# mach_master.net
KiCad netlist of a schematic drawn in Altium Designer
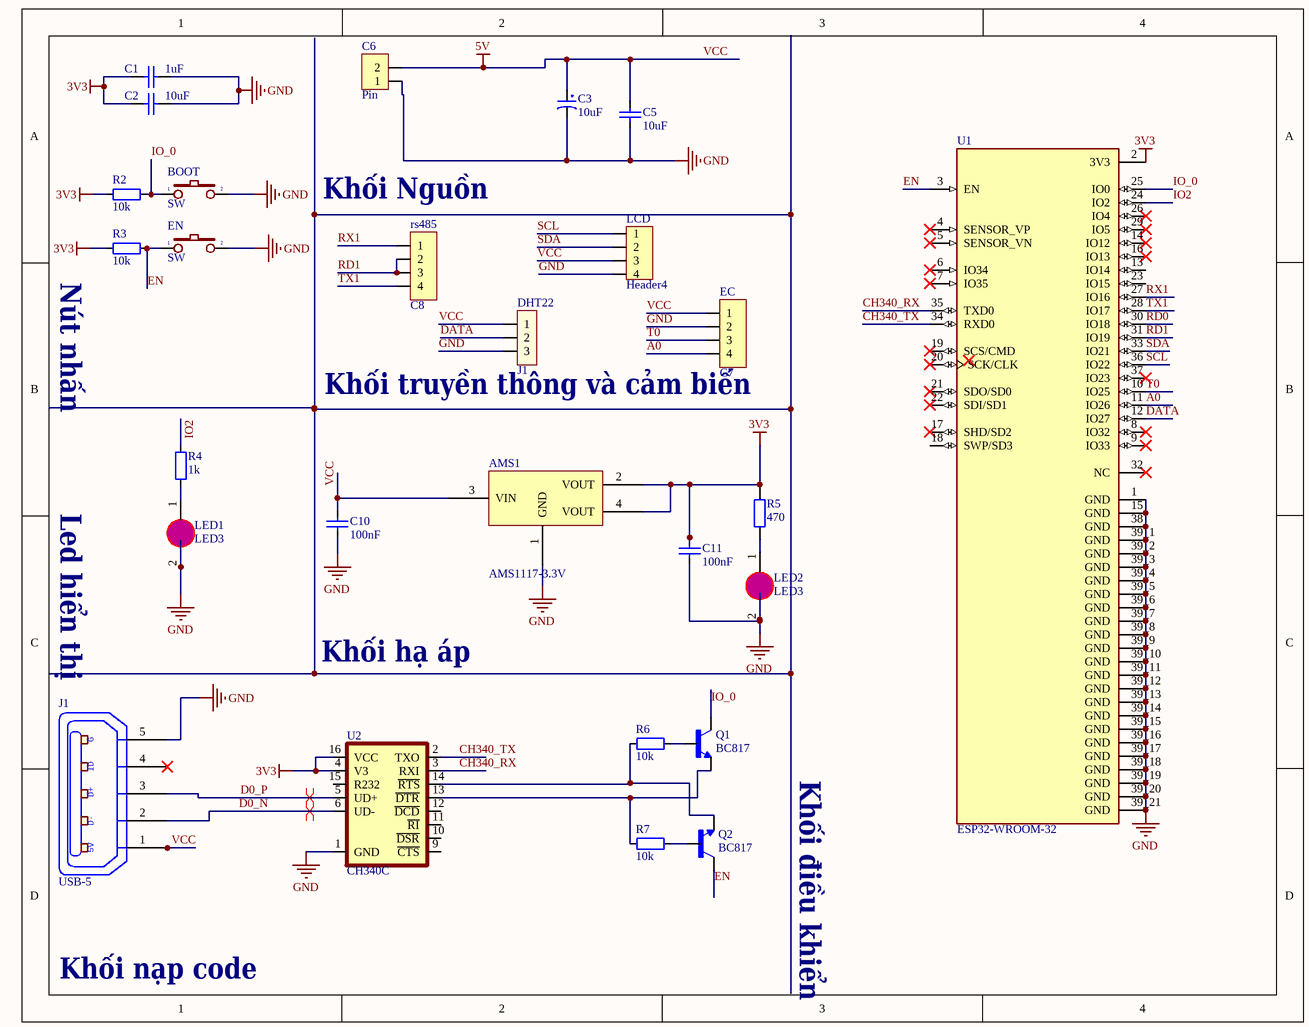
[diagram p0: mach master.SchDoc]

(export (version "E")
  (design (tool "Eeschema 10.0.6"))
  (components
    (comp (ref "AMS1")
      (value "AMS1117-3.3V")
      (footprint "SOT223")
      (description "Dán")
      (libsource (lib "IC") (part "AMS1117 SMD"))
    )
    (comp (ref "BOOT")
      (value "SW")
      (footprint "SW-SMD")
      (description "Switch button 2 pin")
      (libsource (lib "My Library") (part "SW2"))
    )
    (comp (ref "C1")
      (value "1uF")
      (footprint "CAP_0805")
      (description "Capacitor")
      (fields (field (name "PUBLISHER") "Altium Limited"))
      (libsource (lib "") (part "CapSMD_1"))
    )
    (comp (ref "C2")
      (value "10uF")
      (footprint "CAP_0805")
      (description "Capacitor")
      (fields (field (name "PUBLISHER") "Altium Limited"))
      (libsource (lib "") (part "CapSMD_1"))
    )
    (comp (ref "C3")
      (value "10uF")
      (footprint "tu tantalum smd3216")
      (description "Dán")
      (libsource (lib "Tu dien") (part "Tu tantalum 10uF 16V SMD3216"))
    )
    (comp (ref "C5")
      (value "10uF")
      (footprint "CAP_0805")
      (description "Capacitor")
      (fields (field (name "PUBLISHER") "Altium Limited"))
      (libsource (lib "My Library") (part "CapSMD"))
    )
    (comp (ref "C6")
      (value "Pin")
      (footprint "KF2-5.08")
      (description "Header IDC, 2 x 1 Pin Vertical 2.54mm Pitch (Non-Boxed, Male)")
      (fields
        (field (name "MANUFACTURER") "Würth Elektronik eiSos GmbH")
        (field (name "PARTNO") "613002143121")
        (field (name "CREATED BY") "Karrer Zheng")
      )
      (libsource (lib "My Library") (part "Header2"))
    )
    (comp (ref "C10")
      (value "100nF")
      (footprint "CAP_0805")
      (description "Capacitor")
      (fields (field (name "PUBLISHER") "Altium Limited"))
      (libsource (lib "My Library") (part "CapSMD"))
    )
    (comp (ref "C11")
      (value "100nF")
      (footprint "CAP_0805")
      (description "Capacitor")
      (fields (field (name "PUBLISHER") "Altium Limited"))
      (libsource (lib "My Library") (part "CapSMD"))
    )
    (comp (ref "DHT22")
      (value "J1")
      (footprint "Header3")
      (description "Jumper 3")
      (libsource (lib "My Library") (part "JP3"))
    )
    (comp (ref "EC")
      (value "C7")
      (footprint "Header4")
      (description "WR-PHD 2.54 mm Angled Socket Header")
      (fields
        (field (name "MANUFACTURER") "Würth Elektronik eiSos GmbH")
        (field (name "PARTNO") "613004143121")
        (field (name "CREATED BY") "Karrer Zheng")
      )
      (libsource (lib "My Library") (part "JP4"))
    )
    (comp (ref "EN")
      (value "SW")
      (footprint "SW-SMD")
      (description "Switch button 2 pin")
      (libsource (lib "My Library") (part "SW2"))
    )
    (comp (ref "J1")
      (value "USB-5")
      (footprint "USB-M1")
      (fields
        (field (name "MANUFACTURER") "FCI")
        (field (name "MANUFACTURER PART NUMBER") "10118193-0001LF")
        (field (name ".CREATOR") "MM")
        (field (name ".CHECKED PCB") "RF")
        (field (name ".CHECKED SCH") "MM")
      )
      (libsource (lib "My Library 2") (part "USB-5"))
    )
    (comp (ref "LCD")
      (value "Header4")
      (footprint "Header4")
      (description "Header IDC, 4 x 1 Pin Vertical 2.54mm Pitch (Non-Boxed, Male)")
      (fields
        (field (name "MANUFACTURER") "Würth Elektronik eiSos GmbH")
        (field (name "PARTNO") "613002143121")
        (field (name "CREATED BY") "Karrer Zheng")
      )
      (libsource (lib "My Library") (part "Header4"))
    )
    (comp (ref "LED1")
      (value "LED3")
      (footprint "LED0805")
      (description "LED SMD 0805")
      (libsource (lib "My Library 2") (part "LED0805"))
    )
    (comp (ref "LED2")
      (value "LED3")
      (footprint "LED0805")
      (description "LED SMD 0805")
      (libsource (lib "My Library 2") (part "LED0805"))
    )
    (comp (ref "Q1")
      (value "BC817")
      (footprint "SOT95P240X97-3N")
      (description "Bipolar (BJT) Transistor NPN 45V 500mA 100MHz 250mW Surface Mount TO-236AB")
      (fields (field (name "MF") "Rectron"))
      (libsource (lib "BC817") (part "BC817"))
    )
    (comp (ref "Q2")
      (value "BC817")
      (footprint "SOT95P240X97-3N")
      (description "Bipolar (BJT) Transistor NPN 45V 500mA 100MHz 250mW Surface Mount TO-236AB")
      (fields (field (name "MF") "Rectron"))
      (libsource (lib "") (part "BC817_1"))
    )
    (comp (ref "R2")
      (value "10k")
      (footprint "RES-SMD-0805")
      (description "Resistor")
      (fields
        (field (name "MANUFACTURER") "Generic Components")
        (field (name "PUBLISHER") "Altium Hobart Technology Centre")
      )
      (libsource (lib "My Library") (part "Resistor - SMD"))
    )
    (comp (ref "R3")
      (value "10k")
      (footprint "RES-SMD-0805")
      (description "Resistor")
      (fields
        (field (name "MANUFACTURER") "Generic Components")
        (field (name "PUBLISHER") "Altium Hobart Technology Centre")
      )
      (libsource (lib "My Library") (part "Resistor - SMD"))
    )
    (comp (ref "R4")
      (value "1k")
      (footprint "RES-SMD-0805")
      (description "Resistor")
      (fields
        (field (name "MANUFACTURER") "Generic Components")
        (field (name "PUBLISHER") "Altium Hobart Technology Centre")
      )
      (libsource (lib "My Library") (part "Resistor - SMD"))
    )
    (comp (ref "R5")
      (value "470")
      (footprint "RES-SMD-0805")
      (description "22")
      (fields
        (field (name "MANUFACTURER") "Generic Components")
        (field (name "PUBLISHER") "Altium Hobart Technology Centre")
      )
      (libsource (lib "") (part "Resistor - SMD_1"))
    )
    (comp (ref "R6")
      (value "10k")
      (footprint "RES-SMD-0805")
      (description "Resistor")
      (fields
        (field (name "MANUFACTURER") "Generic Components")
        (field (name "PUBLISHER") "Altium Hobart Technology Centre")
      )
      (libsource (lib "My Library") (part "Resistor - SMD"))
    )
    (comp (ref "R7")
      (value "10k")
      (footprint "RES-SMD-0805")
      (description "Resistor")
      (fields
        (field (name "MANUFACTURER") "Generic Components")
        (field (name "PUBLISHER") "Altium Hobart Technology Centre")
      )
      (libsource (lib "My Library") (part "Resistor - SMD"))
    )
    (comp (ref "rs485")
      (value "C8")
      (footprint "Header4")
      (description "WR-PHD 2.54 mm Angled Socket Header")
      (fields
        (field (name "MANUFACTURER") "Würth Elektronik eiSos GmbH")
        (field (name "PARTNO") "613004143121")
        (field (name "CREATED BY") "Karrer Zheng")
      )
      (libsource (lib "My Library") (part "JP4"))
    )
    (comp (ref "U1")
      (value "ESP32-WROOM-32")
      (footprint "MODULE_ESP32-WROOM-32")
      (fields (field (name "MF") "Espressif Systems"))
      (libsource (lib "ESP32-WROOM-32") (part "ESP32-WROOM-32"))
    )
    (comp (ref "U2")
      (value "CH340C")
      (footprint "SOP-16")
      (description "USB to serial chip CH340")
      (fields (field (name "MF") "WCH"))
      (libsource (lib "My Library") (part "CH340C"))
    )
  )
  (nets
    (net (code "1") (name "/A0") (class "Default")
      (node (ref "EC") (pin "4") (pinfunction "4_4") (pintype "passive"))
      (node (ref "U1") (pin "11") (pinfunction "IO26_11") (pintype "bidirectional"))
    )
    (net (code "2") (name "/CH340_RX") (class "Default")
      (node (ref "U1") (pin "35") (pinfunction "TXD0_35") (pintype "bidirectional"))
      (node (ref "U2") (pin "3") (pinfunction "RXI_3") (pintype "bidirectional"))
    )
    (net (code "3") (name "/CH340_TX") (class "Default")
      (node (ref "U1") (pin "34") (pinfunction "RXD0_34") (pintype "bidirectional"))
      (node (ref "U2") (pin "2") (pinfunction "TXO_2") (pintype "bidirectional"))
    )
    (net (code "4") (name "/D0_N") (class "Default")
      (node (ref "J1") (pin "2") (pinfunction "P2_2") (pintype "passive"))
      (node (ref "U2") (pin "6") (pinfunction "UD-_6") (pintype "bidirectional"))
    )
    (net (code "5") (name "/D0_P") (class "Default")
      (node (ref "J1") (pin "3") (pinfunction "P3_3") (pintype "passive"))
      (node (ref "U2") (pin "5") (pinfunction "UD+_5") (pintype "bidirectional"))
    )
    (net (code "6") (name "/DATA") (class "Default")
      (node (ref "DHT22") (pin "2") (pinfunction "2_2") (pintype "passive"))
      (node (ref "U1") (pin "12") (pinfunction "IO27_12") (pintype "bidirectional"))
    )
    (net (code "7") (name "/EN") (class "Default")
      (node (ref "EN") (pin "1") (pinfunction "1_1") (pintype "passive"))
      (node (ref "Q2") (pin "3") (pinfunction "C_3") (pintype "passive"))
      (node (ref "R3") (pin "1") (pinfunction "1_1") (pintype "passive"))
      (node (ref "U1") (pin "3") (pinfunction "EN_3") (pintype "input"))
    )
    (net (code "8") (name "/IO2") (class "Default")
      (node (ref "R4") (pin "2") (pinfunction "2_2") (pintype "passive"))
      (node (ref "U1") (pin "24") (pinfunction "IO2_24") (pintype "bidirectional"))
    )
    (net (code "9") (name "/IO_0") (class "Default")
      (node (ref "BOOT") (pin "1") (pinfunction "1_1") (pintype "passive"))
      (node (ref "Q1") (pin "3") (pinfunction "C_3") (pintype "passive"))
      (node (ref "R2") (pin "1") (pinfunction "1_1") (pintype "passive"))
      (node (ref "U1") (pin "25") (pinfunction "IO0_25") (pintype "bidirectional"))
    )
    (net (code "10") (name "/RD0") (class "Default")
      (node (ref "U1") (pin "30") (pinfunction "IO18_30") (pintype "bidirectional"))
    )
    (net (code "11") (name "/RD1") (class "Default")
      (node (ref "U1") (pin "31") (pinfunction "IO19_31") (pintype "bidirectional"))
      (node (ref "rs485") (pin "2") (pinfunction "2_2") (pintype "passive"))
      (node (ref "rs485") (pin "3") (pinfunction "3_3") (pintype "passive"))
    )
    (net (code "12") (name "/RX1") (class "Default")
      (node (ref "U1") (pin "27") (pinfunction "IO16_27") (pintype "bidirectional"))
      (node (ref "rs485") (pin "1") (pinfunction "1_1") (pintype "passive"))
    )
    (net (code "13") (name "/SCL") (class "Default")
      (node (ref "LCD") (pin "1") (pinfunction "1_1") (pintype "passive"))
      (node (ref "U1") (pin "36") (pinfunction "IO22_36") (pintype "bidirectional"))
    )
    (net (code "14") (name "/SDA") (class "Default")
      (node (ref "LCD") (pin "2") (pinfunction "2_2") (pintype "passive"))
      (node (ref "U1") (pin "33") (pinfunction "IO21_33") (pintype "bidirectional"))
    )
    (net (code "15") (name "/T0") (class "Default")
      (node (ref "EC") (pin "3") (pinfunction "3_3") (pintype "passive"))
      (node (ref "U1") (pin "10") (pinfunction "IO25_10") (pintype "bidirectional"))
    )
    (net (code "16") (name "/TX1") (class "Default")
      (node (ref "U1") (pin "28") (pinfunction "IO17_28") (pintype "bidirectional"))
      (node (ref "rs485") (pin "4") (pinfunction "4_4") (pintype "passive"))
    )
    (net (code "17") (name "3V3") (class "Default")
      (node (ref "AMS1") (pin "2") (pinfunction "VOUT_2") (pintype "passive"))
      (node (ref "AMS1") (pin "4") (pinfunction "VOUT_4") (pintype "passive"))
      (node (ref "C1") (pin "1") (pinfunction "1_1") (pintype "passive"))
      (node (ref "C11") (pin "2") (pinfunction "2_2") (pintype "passive"))
      (node (ref "C2") (pin "1") (pinfunction "1_1") (pintype "passive"))
      (node (ref "R2") (pin "2") (pinfunction "2_2") (pintype "passive"))
      (node (ref "R3") (pin "2") (pinfunction "2_2") (pintype "passive"))
      (node (ref "R5") (pin "1") (pinfunction "1_1") (pintype "passive"))
      (node (ref "U1") (pin "2") (pinfunction "3V3_2") (pintype "power_in"))
      (node (ref "U2") (pin "16") (pinfunction "VCC_16") (pintype "bidirectional"))
      (node (ref "U2") (pin "4") (pinfunction "V3_4") (pintype "bidirectional"))
    )
    (net (code "18") (name "5V") (class "Default")
      (node (ref "AMS1") (pin "3") (pinfunction "VIN_3") (pintype "passive"))
      (node (ref "C10") (pin "2") (pinfunction "2_2") (pintype "passive"))
      (node (ref "C3") (pin "1") (pinfunction "1_1") (pintype "passive"))
      (node (ref "C5") (pin "2") (pinfunction "2_2") (pintype "passive"))
      (node (ref "C6") (pin "2") (pinfunction "2_2") (pintype "passive"))
      (node (ref "DHT22") (pin "1") (pinfunction "1_1") (pintype "passive"))
      (node (ref "EC") (pin "1") (pinfunction "1_1") (pintype "passive"))
      (node (ref "J1") (pin "1") (pinfunction "P1_1") (pintype "passive"))
      (node (ref "LCD") (pin "3") (pinfunction "3_3") (pintype "passive"))
    )
    (net (code "19") (name "GND") (class "Default")
      (node (ref "AMS1") (pin "1") (pinfunction "GND_1") (pintype "passive"))
      (node (ref "BOOT") (pin "2") (pinfunction "2_2") (pintype "passive"))
      (node (ref "C1") (pin "2") (pinfunction "2_2") (pintype "passive"))
      (node (ref "C10") (pin "1") (pinfunction "1_1") (pintype "passive"))
      (node (ref "C11") (pin "1") (pinfunction "1_1") (pintype "passive"))
      (node (ref "C2") (pin "2") (pinfunction "2_2") (pintype "passive"))
      (node (ref "C3") (pin "2") (pinfunction "2_2") (pintype "passive"))
      (node (ref "C5") (pin "1") (pinfunction "1_1") (pintype "passive"))
      (node (ref "C6") (pin "1") (pinfunction "1_1") (pintype "passive"))
      (node (ref "DHT22") (pin "3") (pinfunction "3_3") (pintype "passive"))
      (node (ref "EC") (pin "2") (pinfunction "2_2") (pintype "passive"))
      (node (ref "EN") (pin "2") (pinfunction "2_2") (pintype "passive"))
      (node (ref "J1") (pin "5") (pinfunction "P5_5") (pintype "passive"))
      (node (ref "LCD") (pin "4") (pinfunction "4_4") (pintype "passive"))
      (node (ref "LED1") (pin "2") (pinfunction "K_2") (pintype "passive"))
      (node (ref "LED2") (pin "2") (pinfunction "K_2") (pintype "passive"))
      (node (ref "U1") (pin "1") (pinfunction "GND_1") (pintype "power_in"))
      (node (ref "U1") (pin "15") (pinfunction "GND_15") (pintype "power_in"))
      (node (ref "U1") (pin "38") (pinfunction "GND_38") (pintype "power_in"))
      (node (ref "U1") (pin "39_1") (pinfunction "GND_39_1") (pintype "power_in"))
      (node (ref "U1") (pin "39_10") (pinfunction "GND_39_10") (pintype "power_in"))
      (node (ref "U1") (pin "39_11") (pinfunction "GND_39_11") (pintype "power_in"))
      (node (ref "U1") (pin "39_12") (pinfunction "GND_39_12") (pintype "power_in"))
      (node (ref "U1") (pin "39_13") (pinfunction "GND_39_13") (pintype "power_in"))
      (node (ref "U1") (pin "39_14") (pinfunction "GND_39_14") (pintype "power_in"))
      (node (ref "U1") (pin "39_15") (pinfunction "GND_39_15") (pintype "power_in"))
      (node (ref "U1") (pin "39_16") (pinfunction "GND_39_16") (pintype "power_in"))
      (node (ref "U1") (pin "39_17") (pinfunction "GND_39_17") (pintype "power_in"))
      (node (ref "U1") (pin "39_18") (pinfunction "GND_39_18") (pintype "power_in"))
      (node (ref "U1") (pin "39_19") (pinfunction "GND_39_19") (pintype "power_in"))
      (node (ref "U1") (pin "39_2") (pinfunction "GND_39_2") (pintype "power_in"))
      (node (ref "U1") (pin "39_20") (pinfunction "GND_39_20") (pintype "power_in"))
      (node (ref "U1") (pin "39_21") (pinfunction "GND_39_21") (pintype "power_in"))
      (node (ref "U1") (pin "39_3") (pinfunction "GND_39_3") (pintype "power_in"))
      (node (ref "U1") (pin "39_4") (pinfunction "GND_39_4") (pintype "power_in"))
      (node (ref "U1") (pin "39_5") (pinfunction "GND_39_5") (pintype "power_in"))
      (node (ref "U1") (pin "39_6") (pinfunction "GND_39_6") (pintype "power_in"))
      (node (ref "U1") (pin "39_7") (pinfunction "GND_39_7") (pintype "power_in"))
      (node (ref "U1") (pin "39_8") (pinfunction "GND_39_8") (pintype "power_in"))
      (node (ref "U1") (pin "39_9") (pinfunction "GND_39_9") (pintype "power_in"))
      (node (ref "U2") (pin "1") (pinfunction "GND_1") (pintype "bidirectional"))
    )
    (net (code "20") (name "Net-(LED1-A)") (class "Default")
      (node (ref "LED1") (pin "1") (pinfunction "A_1") (pintype "passive"))
      (node (ref "R4") (pin "1") (pinfunction "1_1") (pintype "passive"))
    )
    (net (code "21") (name "Net-(LED2-A)") (class "Default")
      (node (ref "LED2") (pin "1") (pinfunction "A_1") (pintype "passive"))
      (node (ref "R5") (pin "2") (pinfunction "2_2") (pintype "passive"))
    )
    (net (code "22") (name "Net-(Q1-B)") (class "Default")
      (node (ref "Q1") (pin "1") (pinfunction "B_1") (pintype "passive"))
      (node (ref "R6") (pin "1") (pinfunction "1_1") (pintype "passive"))
    )
    (net (code "23") (name "Net-(Q1-E)") (class "Default")
      (node (ref "Q1") (pin "2") (pinfunction "E_2") (pintype "passive"))
      (node (ref "R7") (pin "2") (pinfunction "2_2") (pintype "passive"))
      (node (ref "U2") (pin "13") (pinfunction "~{DTR}_13") (pintype "bidirectional"))
    )
    (net (code "24") (name "Net-(Q2-B)") (class "Default")
      (node (ref "Q2") (pin "1") (pinfunction "B_1") (pintype "passive"))
      (node (ref "R7") (pin "1") (pinfunction "1_1") (pintype "passive"))
    )
    (net (code "25") (name "Net-(Q2-E)") (class "Default")
      (node (ref "Q2") (pin "2") (pinfunction "E_2") (pintype "passive"))
      (node (ref "R6") (pin "2") (pinfunction "2_2") (pintype "passive"))
      (node (ref "U2") (pin "14") (pinfunction "~{RTS}_14") (pintype "bidirectional"))
    )
    (net (code "26") (name "unconnected-(J1-P4-Pad4)") (class "Default")
      (node (ref "J1") (pin "4") (pinfunction "P4_4") (pintype "passive+no_connect"))
    )
    (net (code "27") (name "unconnected-(U1-IO4-Pad26)") (class "Default")
      (node (ref "U1") (pin "26") (pinfunction "IO4_26") (pintype "bidirectional+no_connect"))
    )
    (net (code "28") (name "unconnected-(U1-IO5-Pad29)") (class "Default")
      (node (ref "U1") (pin "29") (pinfunction "IO5_29") (pintype "bidirectional+no_connect"))
    )
    (net (code "29") (name "unconnected-(U1-IO12-Pad14)") (class "Default")
      (node (ref "U1") (pin "14") (pinfunction "IO12_14") (pintype "bidirectional+no_connect"))
    )
    (net (code "30") (name "unconnected-(U1-IO13-Pad16)") (class "Default")
      (node (ref "U1") (pin "16") (pinfunction "IO13_16") (pintype "bidirectional+no_connect"))
    )
    (net (code "31") (name "unconnected-(U1-IO14-Pad13)") (class "Default")
      (node (ref "U1") (pin "13") (pinfunction "IO14_13") (pintype "bidirectional"))
    )
    (net (code "32") (name "unconnected-(U1-IO15-Pad23)") (class "Default")
      (node (ref "U1") (pin "23") (pinfunction "IO15_23") (pintype "bidirectional"))
    )
    (net (code "33") (name "unconnected-(U1-IO23-Pad37)") (class "Default")
      (node (ref "U1") (pin "37") (pinfunction "IO23_37") (pintype "bidirectional+no_connect"))
    )
    (net (code "34") (name "unconnected-(U1-IO32-Pad8)") (class "Default")
      (node (ref "U1") (pin "8") (pinfunction "IO32_8") (pintype "bidirectional+no_connect"))
    )
    (net (code "35") (name "unconnected-(U1-IO33-Pad9)") (class "Default")
      (node (ref "U1") (pin "9") (pinfunction "IO33_9") (pintype "bidirectional+no_connect"))
    )
    (net (code "36") (name "unconnected-(U1-IO34-Pad6)") (class "Default")
      (node (ref "U1") (pin "6") (pinfunction "IO34_6") (pintype "input+no_connect"))
    )
    (net (code "37") (name "unconnected-(U1-IO35-Pad7)") (class "Default")
      (node (ref "U1") (pin "7") (pinfunction "IO35_7") (pintype "input+no_connect"))
    )
    (net (code "38") (name "unconnected-(U1-NC-Pad32)") (class "Default")
      (node (ref "U1") (pin "32") (pinfunction "NC_32") (pintype "passive+no_connect"))
    )
    (net (code "39") (name "unconnected-(U1-SCK{slash}CLK-Pad20)") (class "Default")
      (node (ref "U1") (pin "20") (pinfunction "SCK/CLK_20") (pintype "bidirectional+no_connect"))
    )
    (net (code "40") (name "unconnected-(U1-SCS{slash}CMD-Pad19)") (class "Default")
      (node (ref "U1") (pin "19") (pinfunction "SCS/CMD_19") (pintype "bidirectional+no_connect"))
    )
    (net (code "41") (name "unconnected-(U1-SDI{slash}SD1-Pad22)") (class "Default")
      (node (ref "U1") (pin "22") (pinfunction "SDI/SD1_22") (pintype "bidirectional+no_connect"))
    )
    (net (code "42") (name "unconnected-(U1-SDO{slash}SD0-Pad21)") (class "Default")
      (node (ref "U1") (pin "21") (pinfunction "SDO/SD0_21") (pintype "bidirectional+no_connect"))
    )
    (net (code "43") (name "unconnected-(U1-SENSOR_VN-Pad5)") (class "Default")
      (node (ref "U1") (pin "5") (pinfunction "SENSOR_VN_5") (pintype "input+no_connect"))
    )
    (net (code "44") (name "unconnected-(U1-SENSOR_VP-Pad4)") (class "Default")
      (node (ref "U1") (pin "4") (pinfunction "SENSOR_VP_4") (pintype "input+no_connect"))
    )
    (net (code "45") (name "unconnected-(U1-SHD{slash}SD2-Pad17)") (class "Default")
      (node (ref "U1") (pin "17") (pinfunction "SHD/SD2_17") (pintype "bidirectional+no_connect"))
    )
    (net (code "46") (name "unconnected-(U1-SWP{slash}SD3-Pad18)") (class "Default")
      (node (ref "U1") (pin "18") (pinfunction "SWP/SD3_18") (pintype "bidirectional"))
    )
    (net (code "47") (name "unconnected-(U2-R232-Pad15)") (class "Default")
      (node (ref "U2") (pin "15") (pinfunction "R232_15") (pintype "bidirectional"))
    )
    (net (code "48") (name "unconnected-(U2-~{CTS}-Pad9)") (class "Default")
      (node (ref "U2") (pin "9") (pinfunction "~{CTS}_9") (pintype "bidirectional"))
    )
    (net (code "49") (name "unconnected-(U2-~{DCD}-Pad12)") (class "Default")
      (node (ref "U2") (pin "12") (pinfunction "~{DCD}_12") (pintype "bidirectional"))
    )
    (net (code "50") (name "unconnected-(U2-~{DSR}-Pad10)") (class "Default")
      (node (ref "U2") (pin "10") (pinfunction "~{DSR}_10") (pintype "bidirectional"))
    )
    (net (code "51") (name "unconnected-(U2-~{RI}-Pad11)") (class "Default")
      (node (ref "U2") (pin "11") (pinfunction "~{RI}_11") (pintype "bidirectional"))
    )
  )
)
